# Melanson_Tech_-_PWM_Generator.net
KiCad netlist of a schematic drawn in Altium Designer
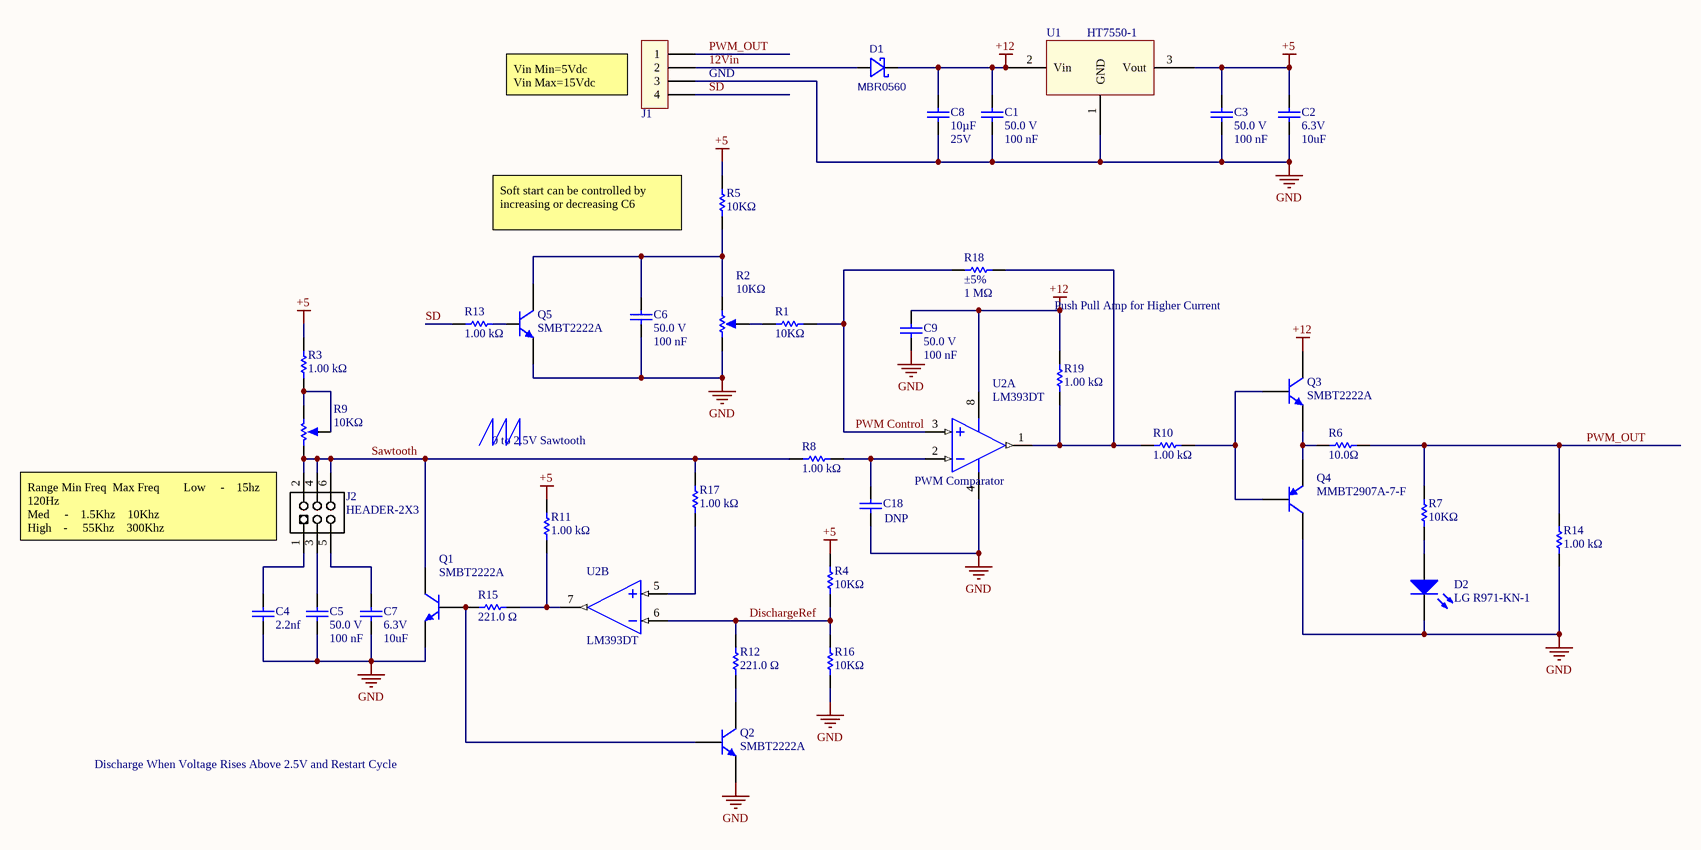
[diagram p0: Melanson Tech - PWM Generator.SchDoc]

(export (version "E")
  (design (tool "Eeschema 10.0.6"))
  (components
    (comp (ref "C1")
      (value "08055C104JAT2A")
      (footprint "Cap,0805")
      (description "Capacitor; Ceramic; Cap 0.1 uF; Tol 5%; Vol-Rtg 50 VDC; SMT; 0805; X7R; Tape & Reel")
      (fields (field (name "VOLTAGE RATING (DC)") "50.0 V") (field (name "CAPACITANCE") "100 nF"))
      (libsource (lib "Master JULY2019") (part "Cap,0805,100nf,50V,5%,08055C104JAT2A"))
    )
    (comp (ref "C2")
      (value "CL21A106KQFNNNG")
      (footprint "Cap,0805")
      (description "CL21 Series 10 uF 6.3V ±10 % Tolerance X5R SMT Multilayer Ceramic Capacitor")
      (fields
        (field (name "TOLERANCE") "±10%")
        (field (name "VOLTAGE - RATED") "6.3V")
        (field (name "CAPACITANCE") "10uF")
      )
      (libsource (lib "Master JULY2019") (part "Cap,0805,10uf,6.3V,10%,CL21A106KQFNNNG"))
    )
    (comp (ref "C3")
      (value "08055C104JAT2A")
      (footprint "Cap,0805")
      (description "Capacitor; Ceramic; Cap 0.1 uF; Tol 5%; Vol-Rtg 50 VDC; SMT; 0805; X7R; Tape & Reel")
      (fields (field (name "VOLTAGE RATING (DC)") "50.0 V") (field (name "CAPACITANCE") "100 nF"))
      (libsource (lib "Master JULY2019") (part "Cap,0805,100nf,50V,5%,08055C104JAT2A"))
    )
    (comp (ref "C4")
      (value "2.2nf")
      (footprint "CAP, 0805, HD")
      (libsource (lib "Master Nov2021") (part "CAP,0805,Generic"))
    )
    (comp (ref "C5")
      (value "08055C104JAT2A")
      (footprint "Cap,0805")
      (description "Capacitor; Ceramic; Cap 0.1 uF; Tol 5%; Vol-Rtg 50 VDC; SMT; 0805; X7R; Tape & Reel")
      (fields (field (name "VOLTAGE RATING (DC)") "50.0 V") (field (name "CAPACITANCE") "100 nF"))
      (libsource (lib "Master JULY2019") (part "Cap,0805,100nf,50V,5%,08055C104JAT2A"))
    )
    (comp (ref "C6")
      (value "08055C104JAT2A")
      (footprint "Cap,0805")
      (description "Capacitor; Ceramic; Cap 0.1 uF; Tol 5%; Vol-Rtg 50 VDC; SMT; 0805; X7R; Tape & Reel")
      (fields (field (name "VOLTAGE RATING (DC)") "50.0 V") (field (name "CAPACITANCE") "100 nF"))
      (libsource (lib "Master JULY2019") (part "Cap,0805,100nf,50V,5%,08055C104JAT2A"))
    )
    (comp (ref "C7")
      (value "CL21A106KQFNNNG")
      (footprint "Cap,0805")
      (description "CL21 Series 10 uF 6.3V ±10 % Tolerance X5R SMT Multilayer Ceramic Capacitor")
      (fields
        (field (name "TOLERANCE") "±10%")
        (field (name "VOLTAGE - RATED") "6.3V")
        (field (name "CAPACITANCE") "10uF")
      )
      (libsource (lib "Master JULY2019") (part "Cap,0805,10uf,6.3V,10%,CL21A106KQFNNNG"))
    )
    (comp (ref "C8")
      (value "C3216X7R1E106K160AB")
      (footprint "Cap, 1206")
      (description "10µF ±10% 25V Ceramic Capacitor X7R 1206 (3216 Metric)")
      (fields
        (field (name "MANUFACTURER") "TDK Corporation")
        (field (name "TOLERANCE") "±10%")
        (field (name "CAPACITANCE") "10µF")
        (field (name "VOLTAGE - RATED") "25V")
      )
      (libsource (lib "Master DEC 2020") (part "CAP,1206,10uF,25V,C3216X7R1E106K160AB"))
    )
    (comp (ref "C9")
      (value "08055C104JAT2A")
      (footprint "Cap,0805")
      (description "Capacitor; Ceramic; Cap 0.1 uF; Tol 5%; Vol-Rtg 50 VDC; SMT; 0805; X7R; Tape & Reel")
      (fields (field (name "VOLTAGE RATING (DC)") "50.0 V") (field (name "CAPACITANCE") "100 nF"))
      (libsource (lib "Master JULY2019") (part "Cap,0805,100nf,50V,5%,08055C104JAT2A"))
    )
    (comp (ref "C18")
      (value "GRM21A5C2E101JW01D")
      (footprint "CAP, 0805, HD")
      (description "CAP CER 100PF 250V 5% NP0 0805")
      (fields (field (name "CAPACITANCE") "DNP"))
      (libsource (lib "Master JULY2019") (part "Cap,0805,100pf,250V,5%,GRM21A5C2E101JW01D"))
    )
    (comp (ref "D1")
      (value "MBR0560")
      (footprint "SOD123")
      (description "Dio,Sig,Schtky,0.5A,60V,SOD123")
      (fields (field (name "MANUFACTURER") "MCC") (field (name "VOLTAGE") "60V"))
      (libsource (lib "Master Mar2021") (part "Diode,SOD123,Shottky,60V,0.5A,MBR0560"))
    )
    (comp (ref "D2")
      (value "LG R971-KN-1")
      (footprint "LED,0805")
      (description "LED GREEN DIFFUSED 0805 SMD")
      (libsource (lib "Master DEC 2020") (part "LED,0805, Green,SMD,LG R971-KN-1"))
    )
    (comp (ref "J1")
      (value "Generic Header")
      (footprint "Header,4POS,0.1\",Vert")
      (description "Generic Header 4 pos header 0.1\"")
      (libsource (lib "Master Nov2021") (part "Header 1x4,0.1{dblquote},TH,Generic"))
    )
    (comp (ref "J2")
      (value "HEADER-2X3")
      (footprint "HEADER-2X3")
      (libsource (lib "TH Connectors") (part "HEADER-2X3"))
    )
    (comp (ref "Q1")
      (value "SMBT2222A")
      (footprint "SOT23-3")
      (description "NPN Silicon Switching Transistor, 40 V VCEO, 600 mA IC, SOT23, Reel, Green")
      (fields (field (name "MFG P/N") "SMBT2222A"))
      (libsource (lib "Master JULY2019") (part "Trans,40V,600mA,0.33W, SMBT2222A"))
    )
    (comp (ref "Q2")
      (value "SMBT2222A")
      (footprint "SOT23-3")
      (description "NPN Silicon Switching Transistor, 40 V VCEO, 600 mA IC, SOT23, Reel, Green")
      (fields (field (name "MFG P/N") "SMBT2222A"))
      (libsource (lib "Master JULY2019") (part "Trans,40V,600mA,0.33W, SMBT2222A"))
    )
    (comp (ref "Q3")
      (value "SMBT2222A")
      (footprint "SOT23-3")
      (description "NPN Silicon Switching Transistor, 40 V VCEO, 600 mA IC, SOT23, Reel, Green")
      (fields (field (name "MFG P/N") "SMBT2222A"))
      (libsource (lib "Master JULY2019") (part "Trans,40V,600mA,0.33W, SMBT2222A"))
    )
    (comp (ref "Q4")
      (value "MMBT2907A-7-F")
      (footprint "SOT23-3")
      (description "TRANS PNP 60V 0.6A SOT23-3")
      (libsource (lib "Master JULY2019") (part "Trans,PNP,60Vdc,600mA,SOT-23-3,MMBT2907A-7-F"))
    )
    (comp (ref "Q5")
      (value "SMBT2222A")
      (footprint "SOT23-3")
      (description "NPN Silicon Switching Transistor, 40 V VCEO, 600 mA IC, SOT23, Reel, Green")
      (fields (field (name "MFG P/N") "SMBT2222A"))
      (libsource (lib "Master JULY2019") (part "Trans,40V,600mA,0.33W, SMBT2222A"))
    )
    (comp (ref "R1")
      (value "Vishay / Dale CRCW080510K0FKTA")
      (footprint "res, 0805, HD")
      (description "RES SMD 10K OHM 1% 1/8W 0805")
      (fields (field (name "RESISTANCE") "10KΩ"))
      (libsource (lib "Master JULY2019") (part "Res,0805,10.0kΩ,1%,100 ppm,CRCW080510K0FKTA"))
    )
    (comp (ref "R2")
      (value "CT94EW103")
      (footprint "Res,TH,POT,TopAdj")
      (description "TRIMMER 10K OHM 0.5W PC PIN TOP")
      (fields
        (field (name "MANUFACTURER") "Nidec Copal Electronics")
        (field (name "TOLERANCE") "±10%")
        (field (name "RESISTANCE") "10KΩ")
      )
      (libsource (lib "Master Mar2021") (part "Res,POT,TH,10KΩ,0.5W,±10%,±100ppm/°C,CT94EW103"))
    )
    (comp (ref "R3")
      (value "Vishay CRCW08051K00JNEA")
      (footprint "res, 0805, HD")
      (description "Res Thick Film 0805 1K Ohm 5% 0.125W(1/8W) ±200ppm/C Molded SMD Automotive Paper T/R")
      (fields
        (field (name "MANUFACTURER PART NUMBER") "CRCW08051K00JNEA")
        (field (name "RESISTANCE") "1.00 kΩ")
      )
      (libsource (lib "Master JULY2019") (part "Res,0805,1.00 kΩ,5%,200ppm,CRCW08051K00JNEA"))
    )
    (comp (ref "R4")
      (value "Vishay / Dale CRCW080510K0FKTA")
      (footprint "res, 0805, HD")
      (description "RES SMD 10K OHM 1% 1/8W 0805")
      (fields (field (name "RESISTANCE") "10KΩ"))
      (libsource (lib "Master JULY2019") (part "Res,0805,10.0kΩ,1%,100 ppm,CRCW080510K0FKTA"))
    )
    (comp (ref "R5")
      (value "Vishay / Dale CRCW080510K0FKTA")
      (footprint "res, 0805, HD")
      (description "RES SMD 10K OHM 1% 1/8W 0805")
      (fields (field (name "RESISTANCE") "10KΩ"))
      (libsource (lib "Master JULY2019") (part "Res,0805,10.0kΩ,1%,100 ppm,CRCW080510K0FKTA"))
    )
    (comp (ref "R6")
      (value "RMCF0805JT10R0")
      (footprint "res, 0805, HD")
      (description "RES 10 OHM 5% 1/8W 0805")
      (fields
        (field (name "MANUFACTURER") "Stackpole Electronics Inc")
        (field (name "TOLERANCE") "±5%")
        (field (name "RESISTANCE") "10.0Ω")
      )
      (libsource (lib "Master JULY2019") (part "Res,0805,10.0Ω,5%,±200ppm/°C,RMCF0805JT10R0"))
    )
    (comp (ref "R7")
      (value "Vishay / Dale CRCW080510K0FKTA")
      (footprint "res, 0805, HD")
      (description "RES SMD 10K OHM 1% 1/8W 0805")
      (fields (field (name "RESISTANCE") "10KΩ"))
      (libsource (lib "Master JULY2019") (part "Res,0805,10.0kΩ,1%,100 ppm,CRCW080510K0FKTA"))
    )
    (comp (ref "R8")
      (value "Vishay CRCW08051K00JNEA")
      (footprint "res, 0805, HD")
      (description "Res Thick Film 0805 1K Ohm 5% 0.125W(1/8W) ±200ppm/C Molded SMD Automotive Paper T/R")
      (fields
        (field (name "MANUFACTURER PART NUMBER") "CRCW08051K00JNEA")
        (field (name "RESISTANCE") "1.00 kΩ")
      )
      (libsource (lib "Master JULY2019") (part "Res,0805,1.00 kΩ,5%,200ppm,CRCW08051K00JNEA"))
    )
    (comp (ref "R9")
      (value "CT94EW103")
      (footprint "Res,TH,POT,TopAdj")
      (description "TRIMMER 10K OHM 0.5W PC PIN TOP")
      (fields
        (field (name "MANUFACTURER") "Nidec Copal Electronics")
        (field (name "TOLERANCE") "±10%")
        (field (name "RESISTANCE") "10KΩ")
      )
      (libsource (lib "Master Mar2021") (part "Res,POT,TH,10KΩ,0.5W,±10%,±100ppm/°C,CT94EW103"))
    )
    (comp (ref "R10")
      (value "Vishay CRCW08051K00JNEA")
      (footprint "res, 0805, HD")
      (description "Res Thick Film 0805 1K Ohm 5% 0.125W(1/8W) ±200ppm/C Molded SMD Automotive Paper T/R")
      (fields
        (field (name "MANUFACTURER PART NUMBER") "CRCW08051K00JNEA")
        (field (name "RESISTANCE") "1.00 kΩ")
      )
      (libsource (lib "Master JULY2019") (part "Res,0805,1.00 kΩ,5%,200ppm,CRCW08051K00JNEA"))
    )
    (comp (ref "R11")
      (value "Vishay CRCW08051K00JNEA")
      (footprint "res, 0805, HD")
      (description "Res Thick Film 0805 1K Ohm 5% 0.125W(1/8W) ±200ppm/C Molded SMD Automotive Paper T/R")
      (fields
        (field (name "MANUFACTURER PART NUMBER") "CRCW08051K00JNEA")
        (field (name "RESISTANCE") "1.00 kΩ")
      )
      (libsource (lib "Master JULY2019") (part "Res,0805,1.00 kΩ,5%,200ppm,CRCW08051K00JNEA"))
    )
    (comp (ref "R12")
      (value "Vishay Dale CRCW0805221RFKTA")
      (footprint "res, 0805, HD")
      (description "RES SMD 221 OHM 1% 1/8W 0805")
      (fields (field (name "RESISTANCE") "221.0 Ω"))
      (libsource (lib "Master Mar2021") (part "Res,0805,221Ω,1%,100ppm,CRCW0805221RFKTA"))
    )
    (comp (ref "R13")
      (value "Vishay CRCW08051K00JNEA")
      (footprint "res, 0805, HD")
      (description "Res Thick Film 0805 1K Ohm 5% 0.125W(1/8W) ±200ppm/C Molded SMD Automotive Paper T/R")
      (fields
        (field (name "MANUFACTURER PART NUMBER") "CRCW08051K00JNEA")
        (field (name "RESISTANCE") "1.00 kΩ")
      )
      (libsource (lib "Master JULY2019") (part "Res,0805,1.00 kΩ,5%,200ppm,CRCW08051K00JNEA"))
    )
    (comp (ref "R14")
      (value "Vishay CRCW08051K00JNEA")
      (footprint "res, 0805, HD")
      (description "Res Thick Film 0805 1K Ohm 5% 0.125W(1/8W) ±200ppm/C Molded SMD Automotive Paper T/R")
      (fields
        (field (name "MANUFACTURER PART NUMBER") "CRCW08051K00JNEA")
        (field (name "RESISTANCE") "1.00 kΩ")
      )
      (libsource (lib "Master JULY2019") (part "Res,0805,1.00 kΩ,5%,200ppm,CRCW08051K00JNEA"))
    )
    (comp (ref "R15")
      (value "Vishay Dale CRCW0805221RFKTA")
      (footprint "res, 0805, HD")
      (description "RES SMD 221 OHM 1% 1/8W 0805")
      (fields (field (name "RESISTANCE") "221.0 Ω"))
      (libsource (lib "Master Mar2021") (part "Res,0805,221Ω,1%,100ppm,CRCW0805221RFKTA"))
    )
    (comp (ref "R16")
      (value "Vishay / Dale CRCW080510K0FKTA")
      (footprint "res, 0805, HD")
      (description "RES SMD 10K OHM 1% 1/8W 0805")
      (fields (field (name "RESISTANCE") "10KΩ"))
      (libsource (lib "Master JULY2019") (part "Res,0805,10.0kΩ,1%,100 ppm,CRCW080510K0FKTA"))
    )
    (comp (ref "R17")
      (value "Vishay CRCW08051K00JNEA")
      (footprint "res, 0805, HD")
      (description "Res Thick Film 0805 1K Ohm 5% 0.125W(1/8W) ±200ppm/C Molded SMD Automotive Paper T/R")
      (fields
        (field (name "MANUFACTURER PART NUMBER") "CRCW08051K00JNEA")
        (field (name "RESISTANCE") "1.00 kΩ")
      )
      (libsource (lib "Master JULY2019") (part "Res,0805,1.00 kΩ,5%,200ppm,CRCW08051K00JNEA"))
    )
    (comp (ref "R18")
      (value "CR0805-JW-105ELF")
      (footprint "res, 0805, HD")
      (description "RES SMD 1M OHM 5% 1/8W 0805")
      (fields
        (field (name "MANUFACTURER") "Bourns Inc.")
        (field (name "JLC ALT LCSC PART #") "C26108")
        (field (name "TOLERANCE") "±5%")
        (field (name "RESISTANCE") "1 MΩ")
      )
      (libsource (lib "Master JULY2019") (part "Res,0805,1MegΩ,5%,200ppm,0805W8F1005T5E"))
    )
    (comp (ref "R19")
      (value "Vishay CRCW08051K00JNEA")
      (footprint "res, 0805, HD")
      (description "Res Thick Film 0805 1K Ohm 5% 0.125W(1/8W) ±200ppm/C Molded SMD Automotive Paper T/R")
      (fields
        (field (name "MANUFACTURER PART NUMBER") "CRCW08051K00JNEA")
        (field (name "RESISTANCE") "1.00 kΩ")
      )
      (libsource (lib "Master JULY2019") (part "Res,0805,1.00 kΩ,5%,200ppm,CRCW08051K00JNEA"))
    )
    (comp (ref "U1")
      (value "HT7550-1")
      (footprint "SOT89-3")
      (description "LOW DROPOUT REGULATORS(LDO) POSITIVE FIXED 55MV @ 1MA 30V 5V 150MA SOT-89(SOT-89-3) ROHS")
      (fields
        (field (name "LCSC PART #") "C16106")
        (field (name "MANUFACTURER") "Holtek Semicon")
        (field (name "MFG P/N") "HT7550-1")
      )
      (libsource (lib "Master DEC 2020") (part "Reg,Linear,Fixed,SOT-89-3,30Vin,5Vout,150mA,HT7550-1"))
    )
    (comp (ref "U2")
      (value "LM393DT")
      (footprint "SOIC-8")
      (description "IC COMPARATOR LP DUAL 8-SOIC")
      (fields (field (name "MANUFACTURER") "STMicroelectronics") (field (name "BASE PART NUMBER") "LM393"))
      (libsource (lib "Master JULY2019") (part "OPAMP,DUAL,COMAPRATOR,SOIC8,OPEN-COLLECTOR,LM393DT"))
    )
  )
  (nets
    (net (code "1") (name "+5") (class "Default")
      (node (ref "C2") (pin "2") (pinfunction "2_2") (pintype "passive"))
      (node (ref "C3") (pin "2") (pinfunction "2_2") (pintype "passive"))
      (node (ref "R11") (pin "2") (pinfunction "2_2") (pintype "passive"))
      (node (ref "R3") (pin "2") (pinfunction "2_2") (pintype "passive"))
      (node (ref "R4") (pin "2") (pinfunction "2_2") (pintype "passive"))
      (node (ref "R5") (pin "2") (pinfunction "2_2") (pintype "passive"))
      (node (ref "U1") (pin "3") (pinfunction "Vout_3") (pintype "passive"))
    )
    (net (code "2") (name "+12") (class "Default")
      (node (ref "C1") (pin "2") (pinfunction "2_2") (pintype "passive"))
      (node (ref "C8") (pin "2") (pinfunction "2_2") (pintype "passive"))
      (node (ref "C9") (pin "2") (pinfunction "2_2") (pintype "passive"))
      (node (ref "D1") (pin "1") (pinfunction "C_1") (pintype "passive"))
      (node (ref "Q3") (pin "3") (pinfunction "C_3") (pintype "passive"))
      (node (ref "R19") (pin "1") (pinfunction "1_1") (pintype "passive"))
      (node (ref "U1") (pin "2") (pinfunction "Vin_2") (pintype "passive"))
      (node (ref "U2") (pin "8") (pinfunction "Vcc_8") (pintype "power_in"))
    )
    (net (code "3") (name "/12Vin") (class "Default")
      (node (ref "D1") (pin "2") (pinfunction "A_2") (pintype "passive"))
      (node (ref "J1") (pin "2") (pinfunction "2_2") (pintype "passive"))
    )
    (net (code "4") (name "/DischargeRef") (class "Default")
      (node (ref "R12") (pin "1") (pinfunction "1_1") (pintype "passive"))
      (node (ref "R16") (pin "2") (pinfunction "2_2") (pintype "passive"))
      (node (ref "R4") (pin "1") (pinfunction "1_1") (pintype "passive"))
      (node (ref "U2") (pin "6") (pinfunction "IN2-_6") (pintype "input"))
    )
    (net (code "5") (name "/PWM Control") (class "Default")
      (node (ref "R1") (pin "1") (pinfunction "1_1") (pintype "passive"))
      (node (ref "R18") (pin "2") (pinfunction "2_2") (pintype "passive"))
      (node (ref "U2") (pin "3") (pinfunction "IN1+_3") (pintype "input"))
    )
    (net (code "6") (name "/PWM_OUT") (class "Default")
      (node (ref "J1") (pin "1") (pinfunction "1_1") (pintype "passive"))
      (node (ref "R14") (pin "1") (pinfunction "1_1") (pintype "passive"))
      (node (ref "R6") (pin "1") (pinfunction "1_1") (pintype "passive"))
      (node (ref "R7") (pin "2") (pinfunction "2_2") (pintype "passive"))
    )
    (net (code "7") (name "/SD") (class "Default")
      (node (ref "J1") (pin "4") (pinfunction "4_4") (pintype "passive"))
      (node (ref "R13") (pin "1") (pinfunction "1_1") (pintype "passive"))
    )
    (net (code "8") (name "/Sawtooth") (class "Default")
      (node (ref "J2") (pin "2") (pintype "passive"))
      (node (ref "J2") (pin "4") (pintype "passive"))
      (node (ref "J2") (pin "6") (pintype "passive"))
      (node (ref "Q1") (pin "3") (pinfunction "C_3") (pintype "passive"))
      (node (ref "R17") (pin "2") (pinfunction "2_2") (pintype "passive"))
      (node (ref "R8") (pin "1") (pinfunction "1_1") (pintype "passive"))
      (node (ref "R9") (pin "1") (pinfunction "1_1") (pintype "passive"))
    )
    (net (code "9") (name "GND") (class "Default")
      (node (ref "C1") (pin "1") (pinfunction "1_1") (pintype "passive"))
      (node (ref "C18") (pin "2") (pinfunction "2_2") (pintype "passive"))
      (node (ref "C2") (pin "1") (pinfunction "1_1") (pintype "passive"))
      (node (ref "C3") (pin "1") (pinfunction "1_1") (pintype "passive"))
      (node (ref "C4") (pin "1") (pinfunction "1_1") (pintype "passive"))
      (node (ref "C5") (pin "1") (pinfunction "1_1") (pintype "passive"))
      (node (ref "C6") (pin "1") (pinfunction "1_1") (pintype "passive"))
      (node (ref "C7") (pin "1") (pinfunction "1_1") (pintype "passive"))
      (node (ref "C8") (pin "1") (pinfunction "1_1") (pintype "passive"))
      (node (ref "C9") (pin "1") (pinfunction "1_1") (pintype "passive"))
      (node (ref "D2") (pin "2") (pinfunction "K_2") (pintype "passive"))
      (node (ref "J1") (pin "3") (pinfunction "3_3") (pintype "passive"))
      (node (ref "Q1") (pin "2") (pinfunction "E_2") (pintype "passive"))
      (node (ref "Q2") (pin "2") (pinfunction "E_2") (pintype "passive"))
      (node (ref "Q4") (pin "3") (pinfunction "C_3") (pintype "passive"))
      (node (ref "Q5") (pin "2") (pinfunction "E_2") (pintype "passive"))
      (node (ref "R14") (pin "2") (pinfunction "2_2") (pintype "passive"))
      (node (ref "R16") (pin "1") (pinfunction "1_1") (pintype "passive"))
      (node (ref "R2") (pin "3") (pinfunction "3_3") (pintype "passive"))
      (node (ref "U1") (pin "1") (pinfunction "GND_1") (pintype "passive"))
      (node (ref "U2") (pin "4") (pinfunction "Gnd_4") (pintype "power_in"))
    )
    (net (code "10") (name "Net-(C4-Pad2)") (class "Default")
      (node (ref "C4") (pin "2") (pinfunction "2_2") (pintype "passive"))
      (node (ref "J2") (pin "1") (pintype "passive"))
    )
    (net (code "11") (name "Net-(C5-Pad2)") (class "Default")
      (node (ref "C5") (pin "2") (pinfunction "2_2") (pintype "passive"))
      (node (ref "J2") (pin "3") (pintype "passive"))
    )
    (net (code "12") (name "Net-(C7-Pad2)") (class "Default")
      (node (ref "C7") (pin "2") (pinfunction "2_2") (pintype "passive"))
      (node (ref "J2") (pin "5") (pintype "passive"))
    )
    (net (code "13") (name "Net-(D2-A)") (class "Default")
      (node (ref "D2") (pin "1") (pinfunction "A_1") (pintype "passive"))
      (node (ref "R7") (pin "1") (pinfunction "1_1") (pintype "passive"))
    )
    (net (code "14") (name "Net-(Q1-B)") (class "Default")
      (node (ref "Q1") (pin "1") (pinfunction "B_1") (pintype "passive"))
      (node (ref "Q2") (pin "1") (pinfunction "B_1") (pintype "passive"))
      (node (ref "R15") (pin "2") (pinfunction "2_2") (pintype "passive"))
    )
    (net (code "15") (name "Net-(Q2-C)") (class "Default")
      (node (ref "Q2") (pin "3") (pinfunction "C_3") (pintype "passive"))
      (node (ref "R12") (pin "2") (pinfunction "2_2") (pintype "passive"))
    )
    (net (code "16") (name "Net-(Q3-B)") (class "Default")
      (node (ref "Q3") (pin "1") (pinfunction "B_1") (pintype "passive"))
      (node (ref "Q4") (pin "1") (pinfunction "B_1") (pintype "passive"))
      (node (ref "R10") (pin "2") (pinfunction "2_2") (pintype "passive"))
    )
    (net (code "17") (name "Net-(Q3-E)") (class "Default")
      (node (ref "Q3") (pin "2") (pinfunction "E_2") (pintype "passive"))
      (node (ref "Q4") (pin "2") (pinfunction "E_2") (pintype "passive"))
      (node (ref "R6") (pin "2") (pinfunction "2_2") (pintype "passive"))
    )
    (net (code "18") (name "Net-(Q5-B)") (class "Default")
      (node (ref "Q5") (pin "1") (pinfunction "B_1") (pintype "passive"))
      (node (ref "R13") (pin "2") (pinfunction "2_2") (pintype "passive"))
    )
    (net (code "19") (name "Net-(Q5-C)") (class "Default")
      (node (ref "C6") (pin "2") (pinfunction "2_2") (pintype "passive"))
      (node (ref "Q5") (pin "3") (pinfunction "C_3") (pintype "passive"))
      (node (ref "R2") (pin "1") (pinfunction "1_1") (pintype "passive"))
      (node (ref "R5") (pin "1") (pinfunction "1_1") (pintype "passive"))
    )
    (net (code "20") (name "Net-(R1-Pad2)") (class "Default")
      (node (ref "R1") (pin "2") (pinfunction "2_2") (pintype "passive"))
      (node (ref "R2") (pin "2") (pinfunction "2_2") (pintype "passive"))
    )
    (net (code "21") (name "Net-(R3-Pad1)") (class "Default")
      (node (ref "R3") (pin "1") (pinfunction "1_1") (pintype "passive"))
      (node (ref "R9") (pin "2") (pinfunction "2_2") (pintype "passive"))
      (node (ref "R9") (pin "3") (pinfunction "3_3") (pintype "passive"))
    )
    (net (code "22") (name "Net-(U2A-IN1-)") (class "Default")
      (node (ref "C18") (pin "1") (pinfunction "1_1") (pintype "passive"))
      (node (ref "R8") (pin "2") (pinfunction "2_2") (pintype "passive"))
      (node (ref "U2") (pin "2") (pinfunction "IN1-_2") (pintype "input"))
    )
    (net (code "23") (name "Net-(U2A-OUT1)") (class "Default")
      (node (ref "R10") (pin "1") (pinfunction "1_1") (pintype "passive"))
      (node (ref "R18") (pin "1") (pinfunction "1_1") (pintype "passive"))
      (node (ref "R19") (pin "2") (pinfunction "2_2") (pintype "passive"))
      (node (ref "U2") (pin "1") (pinfunction "OUT1_1") (pintype "output"))
    )
    (net (code "24") (name "Net-(U2B-IN2+)") (class "Default")
      (node (ref "R17") (pin "1") (pinfunction "1_1") (pintype "passive"))
      (node (ref "U2") (pin "5") (pinfunction "IN2+_5") (pintype "input"))
    )
    (net (code "25") (name "Net-(U2B-OUT2)") (class "Default")
      (node (ref "R11") (pin "1") (pinfunction "1_1") (pintype "passive"))
      (node (ref "R15") (pin "1") (pinfunction "1_1") (pintype "passive"))
      (node (ref "U2") (pin "7") (pinfunction "OUT2_7") (pintype "output"))
    )
  )
)
